# Current-LoadSwitches_5V0.net
KiCad netlist of a schematic drawn in Altium Designer
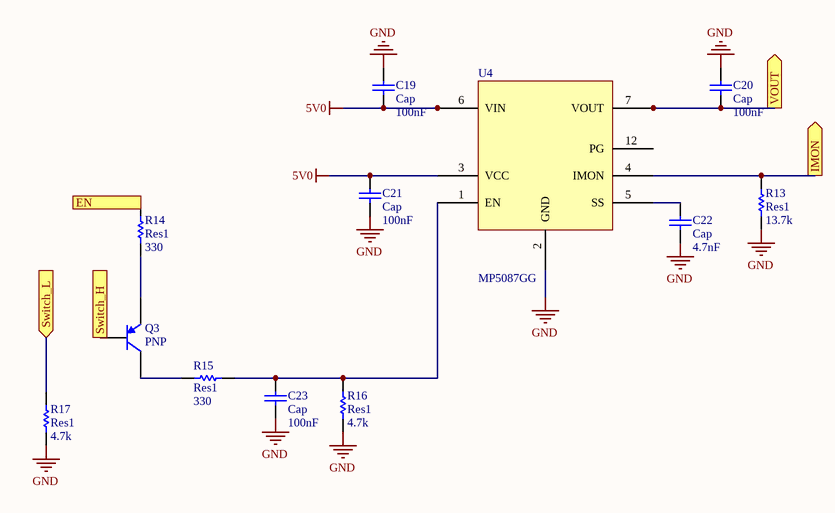
[diagram p0: Current-LoadSwitches 5V0.SchDoc]

(export (version "E")
  (design (tool "Eeschema 10.0.6"))
  (components
    (comp (ref "C19")
      (value "Cap")
      (footprint "1608[0603]")
      (description "Capacitor")
      (fields (field (name "ALTIUM_VALUE") "100nF") (field (name "PUBLISHER") "Altium Limited"))
      (libsource (lib "Miscellaneous Devices") (part "Cap"))
    )
    (comp (ref "C20")
      (value "Cap")
      (footprint "1608[0603]")
      (description "Capacitor")
      (fields (field (name "ALTIUM_VALUE") "100nF") (field (name "PUBLISHER") "Altium Limited"))
      (libsource (lib "Miscellaneous Devices") (part "Cap"))
    )
    (comp (ref "C21")
      (value "Cap")
      (footprint "1608[0603]")
      (description "Capacitor")
      (fields (field (name "ALTIUM_VALUE") "100nF") (field (name "PUBLISHER") "Altium Limited"))
      (libsource (lib "Miscellaneous Devices") (part "Cap"))
    )
    (comp (ref "C22")
      (value "Cap")
      (footprint "1608[0603]")
      (description "Capacitor")
      (fields (field (name "ALTIUM_VALUE") "4.7nF") (field (name "PUBLISHER") "Altium Limited"))
      (libsource (lib "Miscellaneous Devices") (part "Cap"))
    )
    (comp (ref "C23")
      (value "Cap")
      (footprint "1608[0603]")
      (description "Capacitor")
      (fields (field (name "ALTIUM_VALUE") "100nF") (field (name "PUBLISHER") "Altium Limited"))
      (libsource (lib "Miscellaneous Devices") (part "Cap"))
    )
    (comp (ref "Q3")
      (value "PNP")
      (footprint "SOT-23B_N")
      (description "PNP Bipolar Transistor")
      (fields (field (name "PUBLISHER") "Altium Limited"))
      (libsource (lib "Miscellaneous Devices") (part "PNP"))
    )
    (comp (ref "R13")
      (value "Res1")
      (footprint "1608[0603]")
      (description "Resistor")
      (fields (field (name "ALTIUM_VALUE") "13.7k") (field (name "PUBLISHER") "Altium Limited"))
      (libsource (lib "Miscellaneous Devices") (part "Res1"))
    )
    (comp (ref "R14")
      (value "Res1")
      (footprint "1608[0603]")
      (description "Resistor")
      (fields (field (name "ALTIUM_VALUE") "330") (field (name "PUBLISHER") "Altium Limited"))
      (libsource (lib "Miscellaneous Devices") (part "Res1"))
    )
    (comp (ref "R15")
      (value "Res1")
      (footprint "1608[0603]")
      (description "Resistor")
      (fields (field (name "ALTIUM_VALUE") "330") (field (name "PUBLISHER") "Altium Limited"))
      (libsource (lib "Miscellaneous Devices") (part "Res1"))
    )
    (comp (ref "R16")
      (value "Res1")
      (footprint "1608[0603]")
      (description "Resistor")
      (fields (field (name "ALTIUM_VALUE") "4.7k") (field (name "PUBLISHER") "Altium Limited"))
      (libsource (lib "Miscellaneous Devices") (part "Res1"))
    )
    (comp (ref "R17")
      (value "Res1")
      (footprint "1608[0603]")
      (description "Resistor")
      (fields (field (name "ALTIUM_VALUE") "4.7k") (field (name "PUBLISHER") "Altium Limited"))
      (libsource (lib "Miscellaneous Devices") (part "Res1"))
    )
    (comp (ref "U4")
      (value "MP5087GG")
      (footprint "MP5087GG-Z")
      (libsource (lib "MP5087GG-Z") (part "Component_1"))
    )
  )
  (nets
    (net (code "1") (name "/EN") (class "Default")
      (node (ref "R14") (pin "2") (pinfunction "2_2") (pintype "passive"))
    )
    (net (code "2") (name "/IMON") (class "Default")
      (node (ref "R13") (pin "2") (pinfunction "2_2") (pintype "passive"))
      (node (ref "U4") (pin "4") (pinfunction "IMON_4") (pintype "passive"))
    )
    (net (code "3") (name "/Switch_H") (class "Default")
      (node (ref "Q3") (pin "2") (pinfunction "B_2") (pintype "passive"))
    )
    (net (code "4") (name "/Switch_L") (class "Default")
      (node (ref "R17") (pin "2") (pinfunction "2_2") (pintype "passive"))
    )
    (net (code "5") (name "/VOUT") (class "Default")
      (node (ref "C20") (pin "1") (pinfunction "1_1") (pintype "passive"))
      (node (ref "U4") (pin "10") (pinfunction "VOUT_10") (pintype "passive"))
      (node (ref "U4") (pin "7") (pinfunction "VOUT_7") (pintype "passive"))
      (node (ref "U4") (pin "8") (pinfunction "VOUT_8") (pintype "passive"))
      (node (ref "U4") (pin "9") (pinfunction "VOUT_9") (pintype "passive"))
    )
    (net (code "6") (name "5V0") (class "Default")
      (node (ref "C19") (pin "1") (pinfunction "1_1") (pintype "passive"))
      (node (ref "C21") (pin "2") (pinfunction "2_2") (pintype "passive"))
      (node (ref "U4") (pin "11") (pinfunction "VOUT_11") (pintype "passive"))
      (node (ref "U4") (pin "3") (pinfunction "VCC_3") (pintype "passive"))
      (node (ref "U4") (pin "6") (pinfunction "VIN_6") (pintype "passive"))
    )
    (net (code "7") (name "GND") (class "Default")
      (node (ref "C19") (pin "2") (pinfunction "2_2") (pintype "passive"))
      (node (ref "C20") (pin "2") (pinfunction "2_2") (pintype "passive"))
      (node (ref "C21") (pin "1") (pinfunction "1_1") (pintype "passive"))
      (node (ref "C22") (pin "1") (pinfunction "1_1") (pintype "passive"))
      (node (ref "C23") (pin "1") (pinfunction "1_1") (pintype "passive"))
      (node (ref "R13") (pin "1") (pinfunction "1_1") (pintype "passive"))
      (node (ref "R16") (pin "1") (pinfunction "1_1") (pintype "passive"))
      (node (ref "R17") (pin "1") (pinfunction "1_1") (pintype "passive"))
      (node (ref "U4") (pin "2") (pinfunction "GND_2") (pintype "passive"))
    )
    (net (code "8") (name "Net-(Q3-C)") (class "Default")
      (node (ref "Q3") (pin "1") (pinfunction "C_1") (pintype "passive"))
      (node (ref "R15") (pin "1") (pinfunction "1_1") (pintype "passive"))
    )
    (net (code "9") (name "Net-(Q3-E)") (class "Default")
      (node (ref "Q3") (pin "3") (pinfunction "E_3") (pintype "passive"))
      (node (ref "R14") (pin "1") (pinfunction "1_1") (pintype "passive"))
    )
    (net (code "10") (name "Net-(U4-EN)") (class "Default")
      (node (ref "C23") (pin "2") (pinfunction "2_2") (pintype "passive"))
      (node (ref "R15") (pin "2") (pinfunction "2_2") (pintype "passive"))
      (node (ref "R16") (pin "2") (pinfunction "2_2") (pintype "passive"))
      (node (ref "U4") (pin "1") (pinfunction "EN_1") (pintype "passive"))
    )
    (net (code "11") (name "Net-(U4-SS)") (class "Default")
      (node (ref "C22") (pin "2") (pinfunction "2_2") (pintype "passive"))
      (node (ref "U4") (pin "5") (pinfunction "SS_5") (pintype "passive"))
    )
    (net (code "12") (name "unconnected-(U4-PG-Pad12)") (class "Default")
      (node (ref "U4") (pin "12") (pinfunction "PG_12") (pintype "passive"))
    )
  )
)
